# carte_electronique_didactique_PittetL02_.net
KiCad netlist of a schematic drawn in Altium Designer
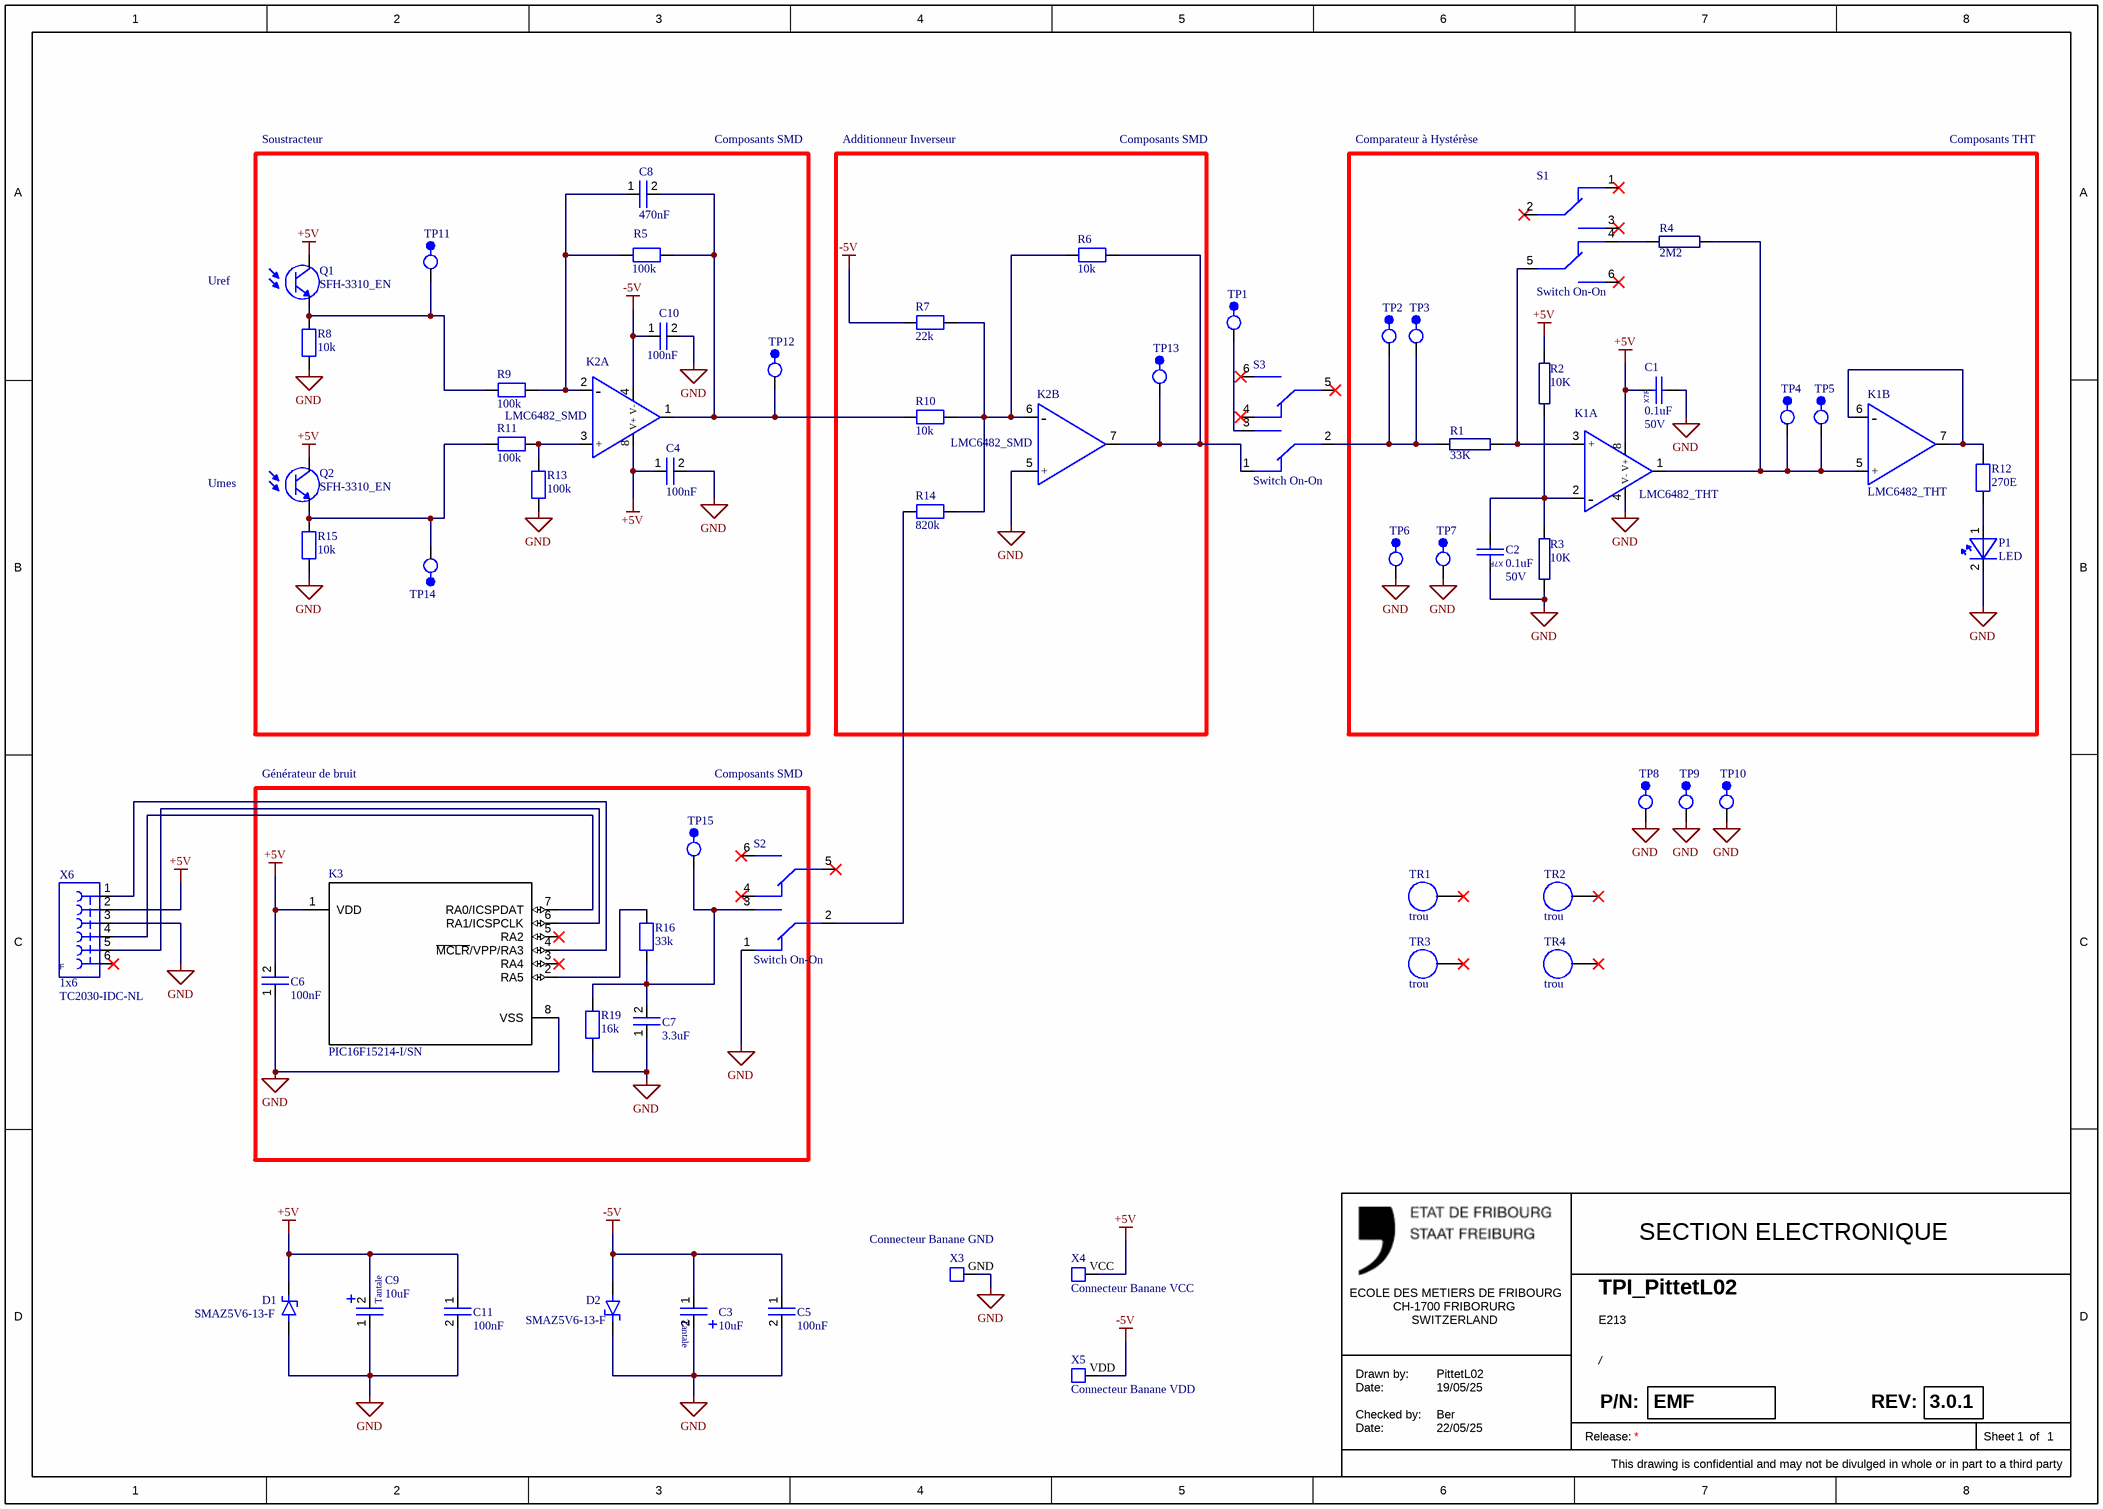
[diagram p0: carte_electronique_didactique_PittetL02_SCH.SchDoc]

(export (version "E")
  (design (tool "Eeschema 10.0.6"))
  (components
    (comp (ref "C1")
      (value "0.1uF")
      (footprint "CTHTNP8x4x11e5")
      (description "C CER X7R 0,1uF/50V 20% DEC (E=5)")
      (fields (field (name "VOLT") "50V"))
      (libsource (lib "EMF_DataBase") (part "E_COND-X7R"))
    )
    (comp (ref "C2")
      (value "0.1uF")
      (footprint "CTHTNP8x4x11e5")
      (description "C CER X7R 0,1uF/50V 20% DEC (E=5)")
      (fields (field (name "VOLT") "50V"))
      (libsource (lib "EMF_DataBase") (part "E_COND-X7R"))
    )
    (comp (ref "C3")
      (value "10uF")
      (footprint "C_0805 tantale")
      (description "0805")
      (libsource (lib "tpi_carte_electronique_didactique_PittetL02") (part "CONDO 1uF Tantale"))
    )
    (comp (ref "C4")
      (value "100nF")
      (footprint "C_0805 ceramique")
      (description "0805")
      (libsource (lib "tpi_carte_electronique_didactique_PittetL02") (part "CONDO 100nf"))
    )
    (comp (ref "C5")
      (value "100nF")
      (footprint "C_0805 ceramique")
      (description "0805")
      (libsource (lib "tpi_carte_electronique_didactique_PittetL02") (part "CONDO 100nf"))
    )
    (comp (ref "C6")
      (value "100nF")
      (footprint "C_0805 ceramique")
      (description "0805")
      (libsource (lib "tpi_carte_electronique_didactique_PittetL02") (part "CONDO 100nf"))
    )
    (comp (ref "C7")
      (value "3.3uF")
      (footprint "C_0805 ceramique")
      (description "0805")
      (libsource (lib "tpi_carte_electronique_didactique_PittetL02") (part "CONDO 100nf"))
    )
    (comp (ref "C8")
      (value "470nF")
      (footprint "C_0805 ceramique")
      (description "0805")
      (libsource (lib "tpi_carte_electronique_didactique_PittetL02") (part "CONDO 100nf"))
    )
    (comp (ref "C9")
      (value "10uF")
      (footprint "C_0805 tantale")
      (description "0805")
      (libsource (lib "tpi_carte_electronique_didactique_PittetL02") (part "CONDO 1uF Tantale"))
    )
    (comp (ref "C10")
      (value "100nF")
      (footprint "C_0805 ceramique")
      (description "0805")
      (libsource (lib "tpi_carte_electronique_didactique_PittetL02") (part "CONDO 100nf"))
    )
    (comp (ref "C11")
      (value "100nF")
      (footprint "C_0805 ceramique")
      (description "0805")
      (libsource (lib "tpi_carte_electronique_didactique_PittetL02") (part "CONDO 100nf"))
    )
    (comp (ref "D1")
      (value "SMAZ5V6-13-F")
      (footprint "DIOM5226X240N")
      (description "Diode zener")
      (fields (field (name "MF") "{'manufacturer': u'Diodes Incorporated'}"))
      (libsource (lib "tpi_carte_electronique_didactique_PittetL02") (part "SMAZ5V6-13-F"))
    )
    (comp (ref "D2")
      (value "SMAZ5V6-13-F")
      (footprint "DIOM5226X240N")
      (description "Diode zener")
      (fields (field (name "MF") "{'manufacturer': u'Diodes Incorporated'}"))
      (libsource (lib "tpi_carte_electronique_didactique_PittetL02") (part "SMAZ5V6-13-F"))
    )
    (comp (ref "K1")
      (value "LMC6482_THT")
      (footprint "LMC6482_THT")
      (libsource (lib "tpi_carte_electronique_didactique_PittetL02") (part "LMC6482_THT"))
    )
    (comp (ref "K2")
      (value "LMC6482_SMD")
      (footprint "LMC6482_SMD")
      (libsource (lib "tpi_carte_electronique_didactique_PittetL02") (part "LMC6482_SMD"))
    )
    (comp (ref "K3")
      (value "PIC16F15214-I/SN")
      (footprint "PIC16F15214-I/SN")
      (libsource (lib "tpi_carte_electronique_didactique_PittetL02") (part "PIC16F15214-I/SN"))
    )
    (comp (ref "P1")
      (value "LED")
      (footprint "LED")
      (libsource (lib "tpi_carte_electronique_didactique_PittetL02") (part "LED"))
    )
    (comp (ref "Q1")
      (value "SFH-3310_EN")
      (footprint "SFH-3310_EN")
      (description "Photo-transistor")
      (libsource (lib "tpi_carte_electronique_didactique_PittetL02") (part "SFH-3310_EN"))
    )
    (comp (ref "Q2")
      (value "SFH-3310_EN")
      (footprint "SFH-3310_EN")
      (description "Photo-transistor")
      (libsource (lib "tpi_carte_electronique_didactique_PittetL02") (part "SFH-3310_EN"))
    )
    (comp (ref "R1")
      (value "33K")
      (footprint "RTHT0250W")
      (description "R METAL 33K  1%  1/2W")
      (fields (field (name "POWER") "0.5W"))
      (libsource (lib "") (part "E_RSTD1_1"))
    )
    (comp (ref "R2")
      (value "10K")
      (footprint "RTHT0250W")
      (description "R METAL 10K  1%  1/2W")
      (fields (field (name "POWER") "0.5W"))
      (libsource (lib "EMF_DataBase") (part "E_RSTD1"))
    )
    (comp (ref "R3")
      (value "10K")
      (footprint "RTHT0250W")
      (description "R METAL 10K  1%  1/2W")
      (fields (field (name "POWER") "0.5W"))
      (libsource (lib "EMF_DataBase") (part "E_RSTD1"))
    )
    (comp (ref "R4")
      (value "2M2")
      (footprint "RTHT0250W")
      (description "R METAL 2M2  1% 1/2W")
      (fields (field (name "POWER") "0.5W"))
      (libsource (lib "") (part "E_RSTD1_1"))
    )
    (comp (ref "R5")
      (value "100k")
      (footprint "Resistances 1206")
      (description "Resistance 1206")
      (fields (field (name "PART NUMBER") "ERA6AEB472V") (field (name "MANUFACTURER") "Panasonic"))
      (libsource (lib "tpi_carte_electronique_didactique_PittetL02") (part "Resistances smd 1206"))
    )
    (comp (ref "R6")
      (value "10k")
      (footprint "Resistances 1206")
      (description "Resistance 1206")
      (fields (field (name "PART NUMBER") "ERA6AEB472V") (field (name "MANUFACTURER") "Panasonic"))
      (libsource (lib "tpi_carte_electronique_didactique_PittetL02") (part "Resistances smd 1206"))
    )
    (comp (ref "R7")
      (value "22k")
      (footprint "Resistances 1206")
      (description "Resistance 1206")
      (fields (field (name "PART NUMBER") "ERA6AEB472V") (field (name "MANUFACTURER") "Panasonic"))
      (libsource (lib "tpi_carte_electronique_didactique_PittetL02") (part "Resistances smd 1206"))
    )
    (comp (ref "R8")
      (value "10k")
      (footprint "Resistances 1206")
      (description "Resistance 1206")
      (fields (field (name "PART NUMBER") "ERA6AEB472V") (field (name "MANUFACTURER") "Panasonic"))
      (libsource (lib "tpi_carte_electronique_didactique_PittetL02") (part "Resistances smd 1206"))
    )
    (comp (ref "R9")
      (value "100k")
      (footprint "Resistances 1206")
      (description "Resistance 1206")
      (fields (field (name "PART NUMBER") "ERA6AEB472V") (field (name "MANUFACTURER") "Panasonic"))
      (libsource (lib "tpi_carte_electronique_didactique_PittetL02") (part "Resistances smd 1206"))
    )
    (comp (ref "R10")
      (value "10k")
      (footprint "Resistances 1206")
      (description "Resistance 1206")
      (fields (field (name "PART NUMBER") "ERA6AEB472V") (field (name "MANUFACTURER") "Panasonic"))
      (libsource (lib "tpi_carte_electronique_didactique_PittetL02") (part "Resistances smd 1206"))
    )
    (comp (ref "R11")
      (value "100k")
      (footprint "Resistances 1206")
      (description "Resistance 1206")
      (fields (field (name "PART NUMBER") "ERA6AEB472V") (field (name "MANUFACTURER") "Panasonic"))
      (libsource (lib "tpi_carte_electronique_didactique_PittetL02") (part "Resistances smd 1206"))
    )
    (comp (ref "R12")
      (value "270E")
      (footprint "Resistances 1206")
      (description "Resistance 1206")
      (fields (field (name "PART NUMBER") "ERA6AEB472V") (field (name "MANUFACTURER") "Panasonic"))
      (libsource (lib "tpi_carte_electronique_didactique_PittetL02") (part "Resistances smd 1206"))
    )
    (comp (ref "R13")
      (value "100k")
      (footprint "Resistances 1206")
      (description "Resistance 1206")
      (fields (field (name "PART NUMBER") "ERA6AEB472V") (field (name "MANUFACTURER") "Panasonic"))
      (libsource (lib "tpi_carte_electronique_didactique_PittetL02") (part "Resistances smd 1206"))
    )
    (comp (ref "R14")
      (value "820k")
      (footprint "Resistances 1206")
      (description "Resistance 1206")
      (fields (field (name "PART NUMBER") "ERA6AEB472V") (field (name "MANUFACTURER") "Panasonic"))
      (libsource (lib "tpi_carte_electronique_didactique_PittetL02") (part "Resistances smd 1206"))
    )
    (comp (ref "R15")
      (value "10k")
      (footprint "Resistances 1206")
      (description "Resistance 1206")
      (fields (field (name "PART NUMBER") "ERA6AEB472V") (field (name "MANUFACTURER") "Panasonic"))
      (libsource (lib "tpi_carte_electronique_didactique_PittetL02") (part "Resistances smd 1206"))
    )
    (comp (ref "R16")
      (value "33k")
      (footprint "Resistances 1206")
      (description "Resistance 1206")
      (fields (field (name "PART NUMBER") "ERA6AEB472V") (field (name "MANUFACTURER") "Panasonic"))
      (libsource (lib "tpi_carte_electronique_didactique_PittetL02") (part "Resistances smd 1206"))
    )
    (comp (ref "R19")
      (value "16k")
      (footprint "Resistances 1206")
      (description "Resistance 1206")
      (fields (field (name "PART NUMBER") "ERA6AEB472V") (field (name "MANUFACTURER") "Panasonic"))
      (libsource (lib "tpi_carte_electronique_didactique_PittetL02") (part "Resistances smd 1206"))
    )
    (comp (ref "S1")
      (value "Switch On-On")
      (footprint "Slide Switches")
      (description "Switch on-on de côté")
      (libsource (lib "tpi_carte_electronique_didactique_PittetL02") (part "Switch On-On"))
    )
    (comp (ref "S2")
      (value "Switch On-On")
      (footprint "Slide Switches")
      (description "Switch on-on de côté")
      (libsource (lib "tpi_carte_electronique_didactique_PittetL02") (part "Switch On-On"))
    )
    (comp (ref "S3")
      (value "Switch On-On")
      (footprint "Slide Switches")
      (description "Switch on-on de côté")
      (libsource (lib "tpi_carte_electronique_didactique_PittetL02") (part "Switch On-On"))
    )
    (comp (ref "TP1")
      (value "TP rouge")
      (footprint "TP10_22")
      (description "Point de test CI isolé rouge")
      (libsource (lib "EMF_DataBase") (part "E_TestPoint_Sonde"))
    )
    (comp (ref "TP2")
      (value "TP rouge")
      (footprint "TP10_22")
      (description "Point de test CI isolé rouge")
      (libsource (lib "EMF_DataBase") (part "E_TestPoint_Sonde"))
    )
    (comp (ref "TP3")
      (value "TP rouge")
      (footprint "TP10_22")
      (description "Point de test CI isolé rouge")
      (libsource (lib "EMF_DataBase") (part "E_TestPoint_Sonde"))
    )
    (comp (ref "TP4")
      (value "TP bleu")
      (footprint "TP10_22")
      (description "Point de test CI isolé bleu")
      (libsource (lib "EMF_DataBase") (part "E_TestPoint_Sonde"))
    )
    (comp (ref "TP5")
      (value "TP bleu")
      (footprint "TP10_22")
      (description "Point de test CI isolé bleu")
      (libsource (lib "EMF_DataBase") (part "E_TestPoint_Sonde"))
    )
    (comp (ref "TP6")
      (value "TP noir")
      (footprint "TP10_22")
      (description "Point de test CI isolé noir")
      (libsource (lib "EMF_DataBase") (part "E_TestPoint_Sonde"))
    )
    (comp (ref "TP7")
      (value "TP noir")
      (footprint "TP10_22")
      (description "Point de test CI isolé noir")
      (libsource (lib "EMF_DataBase") (part "E_TestPoint_Sonde"))
    )
    (comp (ref "TP8")
      (value "TP noir")
      (footprint "TP10_22")
      (description "Point de test CI isolé noir")
      (libsource (lib "EMF_DataBase") (part "E_TestPoint_Sonde"))
    )
    (comp (ref "TP9")
      (value "TP noir")
      (footprint "TP10_22")
      (description "Point de test CI isolé noir")
      (libsource (lib "EMF_DataBase") (part "E_TestPoint_Sonde"))
    )
    (comp (ref "TP10")
      (value "TP noir")
      (footprint "TP10_22")
      (description "Point de test CI isolé noir")
      (libsource (lib "EMF_DataBase") (part "E_TestPoint_Sonde"))
    )
    (comp (ref "TP11")
      (value "TP rouge")
      (footprint "TP10_22")
      (description "Point de test CI isolé rouge")
      (libsource (lib "EMF_DataBase") (part "E_TestPoint_Sonde"))
    )
    (comp (ref "TP12")
      (value "TP rouge")
      (footprint "TP10_22")
      (description "Point de test CI isolé rouge")
      (libsource (lib "EMF_DataBase") (part "E_TestPoint_Sonde"))
    )
    (comp (ref "TP13")
      (value "TP rouge")
      (footprint "TP10_22")
      (description "Point de test CI isolé rouge")
      (libsource (lib "EMF_DataBase") (part "E_TestPoint_Sonde"))
    )
    (comp (ref "TP14")
      (value "TP rouge")
      (footprint "TP10_22")
      (description "Point de test CI isolé rouge")
      (libsource (lib "EMF_DataBase") (part "E_TestPoint_Sonde"))
    )
    (comp (ref "TP15")
      (value "TP rouge")
      (footprint "TP10_22")
      (description "Point de test CI isolé rouge")
      (libsource (lib "EMF_DataBase") (part "E_TestPoint_Sonde"))
    )
    (comp (ref "TR1")
      (value "trou")
      (footprint "trou")
      (libsource (lib "tpi_carte_electronique_didactique_PittetL02") (part "trou"))
    )
    (comp (ref "TR2")
      (value "trou")
      (footprint "trou")
      (libsource (lib "tpi_carte_electronique_didactique_PittetL02") (part "trou"))
    )
    (comp (ref "TR3")
      (value "trou")
      (footprint "trou")
      (libsource (lib "tpi_carte_electronique_didactique_PittetL02") (part "trou"))
    )
    (comp (ref "TR4")
      (value "trou")
      (footprint "trou")
      (libsource (lib "tpi_carte_electronique_didactique_PittetL02") (part "trou"))
    )
    (comp (ref "X3")
      (value "Connecteur Banane GND")
      (footprint "CT3151-0")
      (libsource (lib "tpi_carte_electronique_didactique_PittetL02") (part "Connecteur Banane GND"))
    )
    (comp (ref "X4")
      (value "Connecteur Banane VCC")
      (footprint "CT3151-2")
      (libsource (lib "tpi_carte_electronique_didactique_PittetL02") (part "Connecteur Banane VCC"))
    )
    (comp (ref "X5")
      (value "Connecteur Banane VDD")
      (footprint "CT3151-4")
      (libsource (lib "tpi_carte_electronique_didactique_PittetL02") (part "Connecteur Banane VDD"))
    )
    (comp (ref "X6")
      (value "1x6")
      (footprint "CONN_TC2030NL")
      (description "Conn. avec plage pour contact à ressort TAG-Connect TC2030-IDC-NL")
      (fields (field (name "MANUFACTURER PART NUMBER 1") "TC2030-IDC-NL"))
      (libsource (lib "EMF_DataBase") (part "E_CONN6C-F"))
    )
  )
  (nets
    (net (code "1") (name "+5V") (class "Default")
      (node (ref "C1") (pin "1") (pinfunction "1_1") (pintype "passive"))
      (node (ref "C11") (pin "1") (pinfunction "1_1") (pintype "passive"))
      (node (ref "C4") (pin "1") (pinfunction "1_1") (pintype "passive"))
      (node (ref "C6") (pin "2") (pinfunction "2_2") (pintype "passive"))
      (node (ref "C9") (pin "2") (pinfunction "2_2") (pintype "passive"))
      (node (ref "D1") (pin "1") (pinfunction "K_1") (pintype "passive"))
      (node (ref "K1") (pin "8") (pinfunction "V+_8") (pintype "passive"))
      (node (ref "K2") (pin "8") (pinfunction "V+_8") (pintype "passive"))
      (node (ref "K3") (pin "1") (pinfunction "VDD_1") (pintype "passive"))
      (node (ref "Q1") (pin "2") (pinfunction "C_2") (pintype "passive"))
      (node (ref "Q2") (pin "2") (pinfunction "C_2") (pintype "passive"))
      (node (ref "R2") (pin "1") (pinfunction "1_1") (pintype "passive"))
      (node (ref "X4") (pin "VCC") (pinfunction "VCC_VCC") (pintype "passive"))
      (node (ref "X6") (pin "2") (pinfunction "2_2") (pintype "passive"))
    )
    (net (code "2") (name "-5V") (class "Default")
      (node (ref "C10") (pin "1") (pinfunction "1_1") (pintype "passive"))
      (node (ref "C3") (pin "1") (pinfunction "1_1") (pintype "passive"))
      (node (ref "C5") (pin "1") (pinfunction "1_1") (pintype "passive"))
      (node (ref "D2") (pin "2") (pinfunction "A_2") (pintype "passive"))
      (node (ref "K2") (pin "4") (pinfunction "V-_4") (pintype "passive"))
      (node (ref "R7") (pin "1") (pinfunction "1_1") (pintype "passive"))
      (node (ref "X5") (pin "VDD") (pinfunction "VDD_VDD") (pintype "passive"))
    )
    (net (code "3") (name "GND") (class "Default")
      (node (ref "C1") (pin "2") (pinfunction "2_2") (pintype "passive"))
      (node (ref "C10") (pin "2") (pinfunction "2_2") (pintype "passive"))
      (node (ref "C11") (pin "2") (pinfunction "2_2") (pintype "passive"))
      (node (ref "C2") (pin "1") (pinfunction "1_1") (pintype "passive"))
      (node (ref "C3") (pin "2") (pinfunction "2_2") (pintype "passive"))
      (node (ref "C4") (pin "2") (pinfunction "2_2") (pintype "passive"))
      (node (ref "C5") (pin "2") (pinfunction "2_2") (pintype "passive"))
      (node (ref "C6") (pin "1") (pinfunction "1_1") (pintype "passive"))
      (node (ref "C7") (pin "1") (pinfunction "1_1") (pintype "passive"))
      (node (ref "C9") (pin "1") (pinfunction "1_1") (pintype "passive"))
      (node (ref "D1") (pin "2") (pinfunction "A_2") (pintype "passive"))
      (node (ref "D2") (pin "1") (pinfunction "K_1") (pintype "passive"))
      (node (ref "K1") (pin "4") (pinfunction "V-_4") (pintype "passive"))
      (node (ref "K2") (pin "5") (pinfunction "+_5") (pintype "passive"))
      (node (ref "K3") (pin "8") (pinfunction "VSS_8") (pintype "passive"))
      (node (ref "P1") (pin "2") (pinfunction "2_2") (pintype "passive"))
      (node (ref "R13") (pin "1") (pinfunction "1_1") (pintype "passive"))
      (node (ref "R15") (pin "1") (pinfunction "1_1") (pintype "passive"))
      (node (ref "R19") (pin "1") (pinfunction "1_1") (pintype "passive"))
      (node (ref "R3") (pin "2") (pinfunction "2_2") (pintype "passive"))
      (node (ref "R8") (pin "1") (pinfunction "1_1") (pintype "passive"))
      (node (ref "S2") (pin "1") (pinfunction "1_1") (pintype "passive"))
      (node (ref "TP10") (pin "1") (pinfunction "a_1") (pintype "passive"))
      (node (ref "TP6") (pin "1") (pinfunction "a_1") (pintype "passive"))
      (node (ref "TP7") (pin "1") (pinfunction "a_1") (pintype "passive"))
      (node (ref "TP8") (pin "1") (pinfunction "a_1") (pintype "passive"))
      (node (ref "TP9") (pin "1") (pinfunction "a_1") (pintype "passive"))
      (node (ref "X3") (pin "GND") (pinfunction "GND_GND") (pintype "passive"))
      (node (ref "X6") (pin "3") (pinfunction "3_3") (pintype "passive"))
    )
    (net (code "4") (name "Net-(K1A-+)") (class "Default")
      (node (ref "K1") (pin "3") (pinfunction "+_3") (pintype "passive"))
      (node (ref "R1") (pin "2") (pinfunction "2_2") (pintype "passive"))
      (node (ref "S1") (pin "5") (pinfunction "5_5") (pintype "passive"))
    )
    (net (code "5") (name "Net-(K1A--)") (class "Default")
      (node (ref "C2") (pin "2") (pinfunction "2_2") (pintype "passive"))
      (node (ref "K1") (pin "2") (pinfunction "-_2") (pintype "passive"))
      (node (ref "R2") (pin "2") (pinfunction "2_2") (pintype "passive"))
      (node (ref "R3") (pin "1") (pinfunction "1_1") (pintype "passive"))
    )
    (net (code "6") (name "Net-(K1B-+)") (class "Default")
      (node (ref "K1") (pin "1") (pinfunction "1_1") (pintype "passive"))
      (node (ref "K1") (pin "5") (pinfunction "+_5") (pintype "passive"))
      (node (ref "R4") (pin "2") (pinfunction "2_2") (pintype "passive"))
      (node (ref "TP4") (pin "1") (pinfunction "a_1") (pintype "passive"))
      (node (ref "TP5") (pin "1") (pinfunction "a_1") (pintype "passive"))
    )
    (net (code "7") (name "Net-(K1B--)") (class "Default")
      (node (ref "K1") (pin "6") (pinfunction "-_6") (pintype "passive"))
      (node (ref "K1") (pin "7") (pinfunction "7_7") (pintype "passive"))
      (node (ref "R12") (pin "1") (pinfunction "1_1") (pintype "passive"))
    )
    (net (code "8") (name "Net-(K2A-+)") (class "Default")
      (node (ref "K2") (pin "3") (pinfunction "+_3") (pintype "passive"))
      (node (ref "R11") (pin "2") (pinfunction "2_2") (pintype "passive"))
      (node (ref "R13") (pin "2") (pinfunction "2_2") (pintype "passive"))
    )
    (net (code "9") (name "Net-(K2A--)") (class "Default")
      (node (ref "C8") (pin "1") (pinfunction "1_1") (pintype "passive"))
      (node (ref "K2") (pin "2") (pinfunction "-_2") (pintype "passive"))
      (node (ref "R5") (pin "1") (pinfunction "1_1") (pintype "passive"))
      (node (ref "R9") (pin "2") (pinfunction "2_2") (pintype "passive"))
    )
    (net (code "10") (name "Net-(K2B--)") (class "Default")
      (node (ref "K2") (pin "6") (pinfunction "-_6") (pintype "passive"))
      (node (ref "R10") (pin "2") (pinfunction "2_2") (pintype "passive"))
      (node (ref "R14") (pin "2") (pinfunction "2_2") (pintype "passive"))
      (node (ref "R6") (pin "1") (pinfunction "1_1") (pintype "passive"))
      (node (ref "R7") (pin "2") (pinfunction "2_2") (pintype "passive"))
    )
    (net (code "11") (name "Net-(K2B-1)") (class "Default")
      (node (ref "K2") (pin "7") (pinfunction "1_7") (pintype "passive"))
      (node (ref "R6") (pin "2") (pinfunction "2_2") (pintype "passive"))
      (node (ref "S3") (pin "1") (pinfunction "1_1") (pintype "passive"))
      (node (ref "TP13") (pin "1") (pinfunction "a_1") (pintype "passive"))
    )
    (net (code "12") (name "Net-(K3-RA0{slash}ICSPDAT)") (class "Default")
      (node (ref "K3") (pin "7") (pinfunction "RA0/ICSPDAT_7") (pintype "bidirectional"))
      (node (ref "X6") (pin "4") (pinfunction "4_4") (pintype "passive"))
    )
    (net (code "13") (name "Net-(K3-RA1{slash}ICSPCLK)") (class "Default")
      (node (ref "K3") (pin "6") (pinfunction "RA1/ICSPCLK_6") (pintype "bidirectional"))
      (node (ref "X6") (pin "5") (pinfunction "5_5") (pintype "passive"))
    )
    (net (code "14") (name "Net-(K3-RA5)") (class "Default")
      (node (ref "K3") (pin "2") (pinfunction "RA5_2") (pintype "bidirectional"))
      (node (ref "R16") (pin "2") (pinfunction "2_2") (pintype "passive"))
    )
    (net (code "15") (name "Net-(K3-~{MCLR}{slash}VPP{slash}RA3)") (class "Default")
      (node (ref "K3") (pin "4") (pinfunction "~{MCLR}/VPP/RA3_4") (pintype "bidirectional"))
      (node (ref "X6") (pin "1") (pinfunction "1_1") (pintype "passive"))
    )
    (net (code "16") (name "Net-(P1-Pad1)") (class "Default")
      (node (ref "P1") (pin "1") (pinfunction "1_1") (pintype "passive"))
      (node (ref "R12") (pin "2") (pinfunction "2_2") (pintype "passive"))
    )
    (net (code "17") (name "Net-(Q1-E)") (class "Default")
      (node (ref "Q1") (pin "1") (pinfunction "E_1") (pintype "passive"))
      (node (ref "R8") (pin "2") (pinfunction "2_2") (pintype "passive"))
      (node (ref "R9") (pin "1") (pinfunction "1_1") (pintype "passive"))
      (node (ref "TP11") (pin "1") (pinfunction "a_1") (pintype "passive"))
    )
    (net (code "18") (name "Net-(Q2-E)") (class "Default")
      (node (ref "Q2") (pin "1") (pinfunction "E_1") (pintype "passive"))
      (node (ref "R11") (pin "1") (pinfunction "1_1") (pintype "passive"))
      (node (ref "R15") (pin "2") (pinfunction "2_2") (pintype "passive"))
      (node (ref "TP14") (pin "1") (pinfunction "a_1") (pintype "passive"))
    )
    (net (code "19") (name "Net-(R4-Pad1)") (class "Default")
      (node (ref "R4") (pin "1") (pinfunction "1_1") (pintype "passive"))
      (node (ref "S1") (pin "4") (pinfunction "4_4") (pintype "passive"))
    )
    (net (code "20") (name "Net-(R14-Pad1)") (class "Default")
      (node (ref "R14") (pin "1") (pinfunction "1_1") (pintype "passive"))
      (node (ref "S2") (pin "2") (pinfunction "2_2") (pintype "passive"))
    )
    (net (code "21") (name "Net-(TP1-a)") (class "Default")
      (node (ref "S3") (pin "3") (pinfunction "3_3") (pintype "passive"))
      (node (ref "TP1") (pin "1") (pinfunction "a_1") (pintype "passive"))
    )
    (net (code "22") (name "Net-(TP2-a)") (class "Default")
      (node (ref "R1") (pin "1") (pinfunction "1_1") (pintype "passive"))
      (node (ref "S3") (pin "2") (pinfunction "2_2") (pintype "passive"))
      (node (ref "TP2") (pin "1") (pinfunction "a_1") (pintype "passive"))
      (node (ref "TP3") (pin "1") (pinfunction "a_1") (pintype "passive"))
    )
    (net (code "23") (name "Net-(TP12-a)") (class "Default")
      (node (ref "C8") (pin "2") (pinfunction "2_2") (pintype "passive"))
      (node (ref "K2") (pin "1") (pinfunction "1_1") (pintype "passive"))
      (node (ref "R10") (pin "1") (pinfunction "1_1") (pintype "passive"))
      (node (ref "R5") (pin "2") (pinfunction "2_2") (pintype "passive"))
      (node (ref "TP12") (pin "1") (pinfunction "a_1") (pintype "passive"))
    )
    (net (code "24") (name "Net-(TP15-a)") (class "Default")
      (node (ref "C7") (pin "2") (pinfunction "2_2") (pintype "passive"))
      (node (ref "R16") (pin "1") (pinfunction "1_1") (pintype "passive"))
      (node (ref "R19") (pin "2") (pinfunction "2_2") (pintype "passive"))
      (node (ref "S2") (pin "3") (pinfunction "3_3") (pintype "passive"))
      (node (ref "TP15") (pin "1") (pinfunction "a_1") (pintype "passive"))
    )
    (net (code "25") (name "unconnected-(K3-RA2-Pad5)") (class "Default")
      (node (ref "K3") (pin "5") (pinfunction "RA2_5") (pintype "bidirectional+no_connect"))
    )
    (net (code "26") (name "unconnected-(K3-RA4-Pad3)") (class "Default")
      (node (ref "K3") (pin "3") (pinfunction "RA4_3") (pintype "bidirectional+no_connect"))
    )
    (net (code "27") (name "unconnected-(S1-Pad1)") (class "Default")
      (node (ref "S1") (pin "1") (pinfunction "1_1") (pintype "passive+no_connect"))
    )
    (net (code "28") (name "unconnected-(S1-Pad2)") (class "Default")
      (node (ref "S1") (pin "2") (pinfunction "2_2") (pintype "passive+no_connect"))
    )
    (net (code "29") (name "unconnected-(S1-Pad3)") (class "Default")
      (node (ref "S1") (pin "3") (pinfunction "3_3") (pintype "passive+no_connect"))
    )
    (net (code "30") (name "unconnected-(S1-Pad6)") (class "Default")
      (node (ref "S1") (pin "6") (pinfunction "6_6") (pintype "passive+no_connect"))
    )
    (net (code "31") (name "unconnected-(S2-Pad4)") (class "Default")
      (node (ref "S2") (pin "4") (pinfunction "4_4") (pintype "passive+no_connect"))
    )
    (net (code "32") (name "unconnected-(S2-Pad5)") (class "Default")
      (node (ref "S2") (pin "5") (pinfunction "5_5") (pintype "passive+no_connect"))
    )
    (net (code "33") (name "unconnected-(S2-Pad6)") (class "Default")
      (node (ref "S2") (pin "6") (pinfunction "6_6") (pintype "passive+no_connect"))
    )
    (net (code "34") (name "unconnected-(S3-Pad4)") (class "Default")
      (node (ref "S3") (pin "4") (pinfunction "4_4") (pintype "passive+no_connect"))
    )
    (net (code "35") (name "unconnected-(S3-Pad5)") (class "Default")
      (node (ref "S3") (pin "5") (pinfunction "5_5") (pintype "passive+no_connect"))
    )
    (net (code "36") (name "unconnected-(S3-Pad6)") (class "Default")
      (node (ref "S3") (pin "6") (pinfunction "6_6") (pintype "passive+no_connect"))
    )
    (net (code "37") (name "unconnected-(TR1-78-Pad1)") (class "Default")
      (node (ref "TR1") (pin "1") (pinfunction "78_1") (pintype "passive+no_connect"))
    )
    (net (code "38") (name "unconnected-(TR2-78-Pad1)") (class "Default")
      (node (ref "TR2") (pin "1") (pinfunction "78_1") (pintype "passive+no_connect"))
    )
    (net (code "39") (name "unconnected-(TR3-78-Pad1)") (class "Default")
      (node (ref "TR3") (pin "1") (pinfunction "78_1") (pintype "passive+no_connect"))
    )
    (net (code "40") (name "unconnected-(TR4-78-Pad1)") (class "Default")
      (node (ref "TR4") (pin "1") (pinfunction "78_1") (pintype "passive+no_connect"))
    )
    (net (code "41") (name "unconnected-(X6-Pad6)") (class "Default")
      (node (ref "X6") (pin "6") (pinfunction "6_6") (pintype "passive+no_connect"))
    )
  )
)
